# Me-Motor_Driver_v2_0.net
KiCad netlist of a schematic drawn in EAGLE
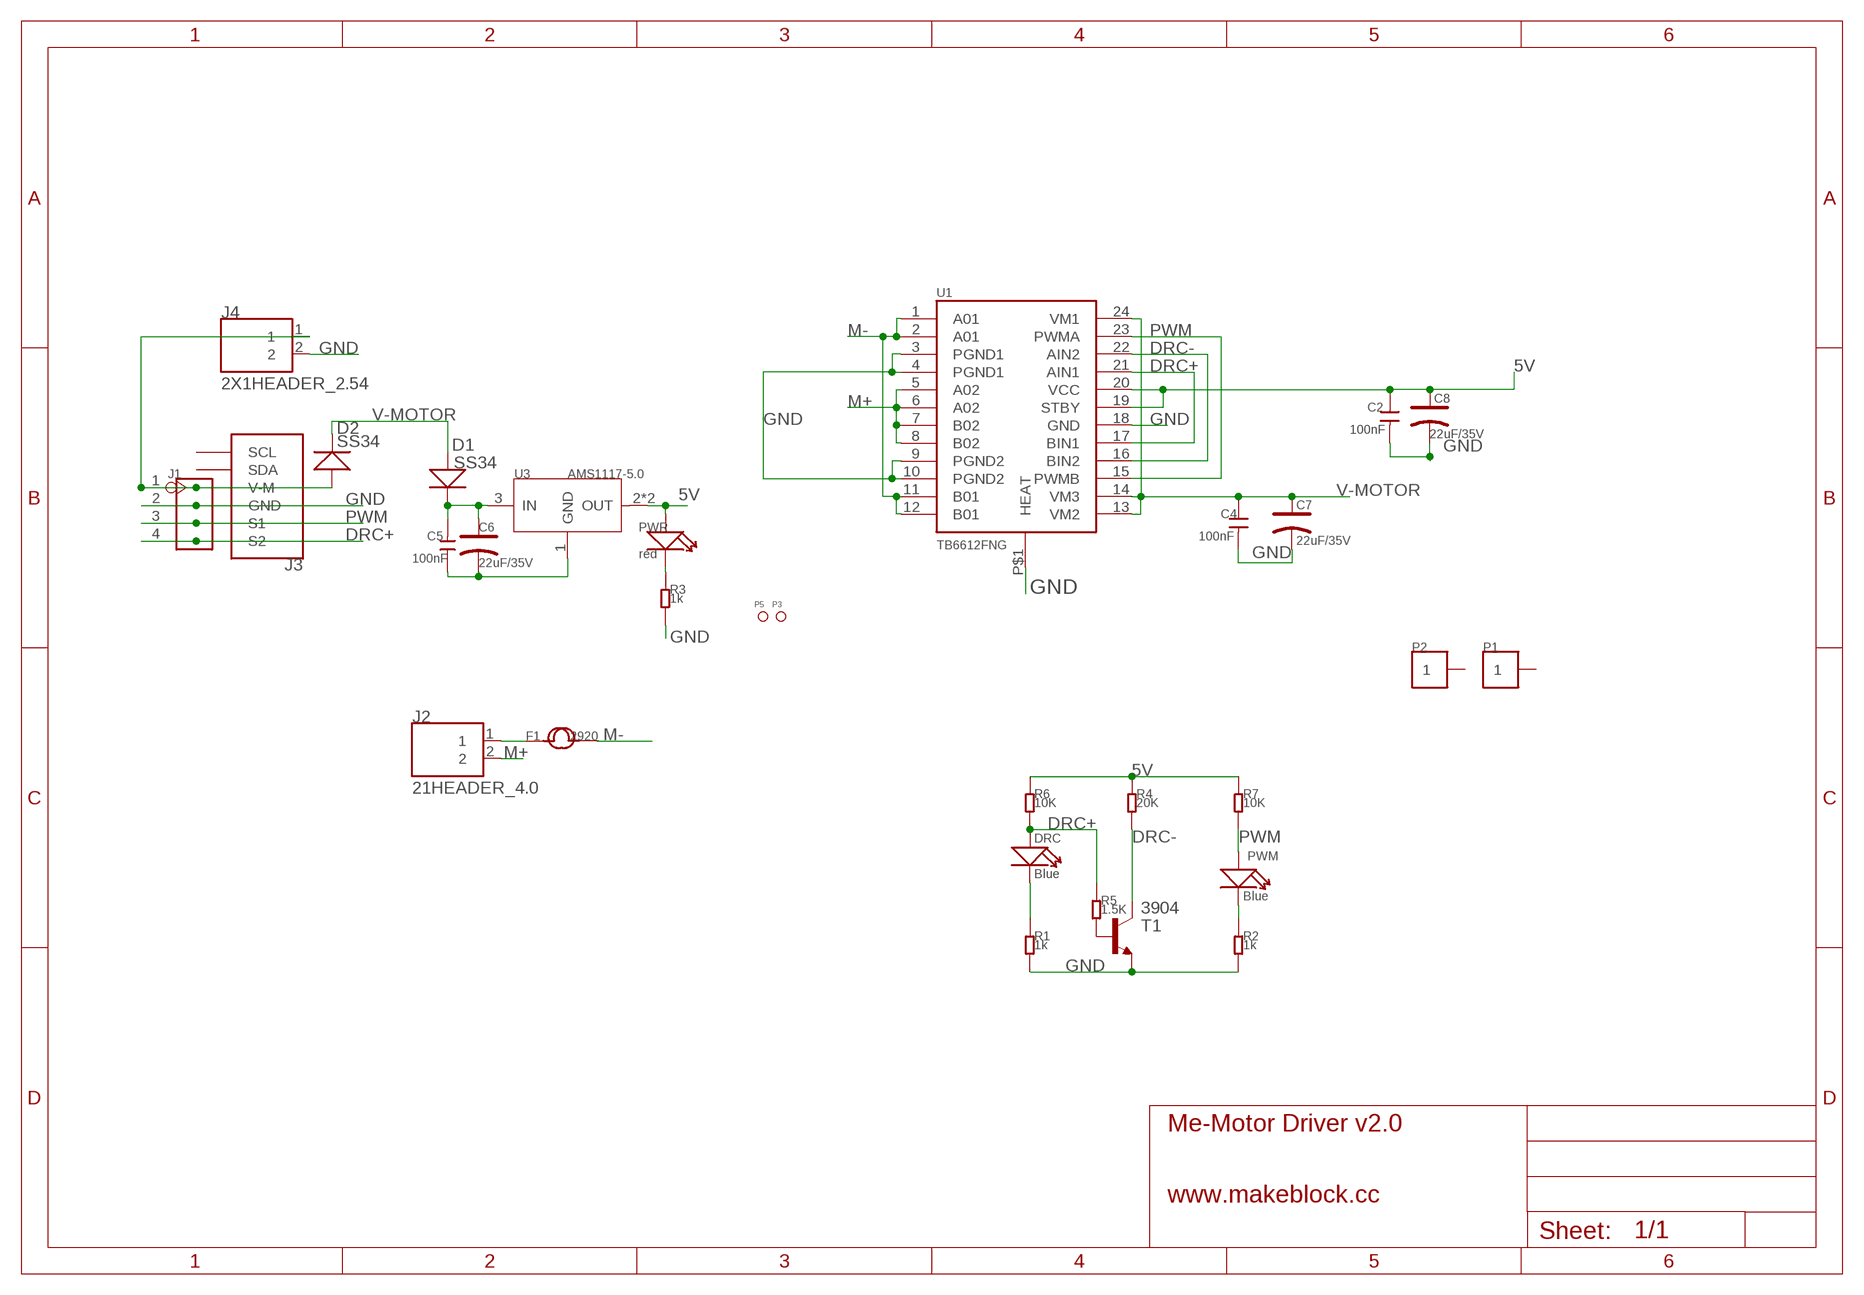
[diagram p0: schematic, sheet 1]

(export (version "E")
  (design (tool "Eeschema 10.0.6"))
  (components
    (comp (ref "C2")
      (value "100nF")
      (footprint "eagle-import:0603_S")
      (libsource (lib "eagle-import") (part "006-C3035"))
    )
    (comp (ref "C4")
      (value "100nF")
      (footprint "eagle-import:0603_S")
      (libsource (lib "eagle-import") (part "006-C3035"))
    )
    (comp (ref "C5")
      (value "100nF")
      (footprint "eagle-import:0603")
      (libsource (lib "eagle-import") (part "C-0603"))
    )
    (comp (ref "C6")
      (value "22uF/35V")
      (footprint "eagle-import:ELECTRO-SMD-B-4.8MM")
      (libsource (lib "eagle-import") (part "CAP-ELECTRO-B"))
    )
    (comp (ref "C7")
      (value "22uF/35V")
      (footprint "eagle-import:ELECTRO-SMD-B-4.8MM")
      (libsource (lib "eagle-import") (part "CAP-ELECTRO-B"))
    )
    (comp (ref "C8")
      (value "22uF/35V")
      (footprint "eagle-import:ELECTRO-SMD-B-4.8MM")
      (libsource (lib "eagle-import") (part "CAP-ELECTRO-B"))
    )
    (comp (ref "D1")
      (value "SS34")
      (footprint "eagle-import:D2010")
      (libsource (lib "eagle-import") (part "D'SMA'"))
    )
    (comp (ref "D2")
      (value "SS34")
      (footprint "eagle-import:D2010")
      (libsource (lib "eagle-import") (part "D'SMA'"))
    )
    (comp (ref "DRC")
      (value "Blue")
      (footprint "eagle-import:LED-0603")
      (libsource (lib "eagle-import") (part "LED'0603'"))
    )
    (comp (ref "F1")
      (value "2920")
      (footprint "eagle-import:2920")
      (libsource (lib "eagle-import") (part "2920"))
    )
    (comp (ref "J1")
      (value "HEADER-4P-60/35MIL")
      (footprint "eagle-import:4P-65_35MIL")
      (libsource (lib "eagle-import") (part "HEADER-4P-60/35MIL"))
    )
    (comp (ref "J2")
      (value "21HEADER_4.0")
      (footprint "eagle-import:2_1HEADER_4.0")
      (libsource (lib "eagle-import") (part "21HEADER_4.0"))
    )
    (comp (ref "J3")
      (value "RJ11-6P6C-MOTOR")
      (footprint "eagle-import:RJ11-6P6C")
      (libsource (lib "eagle-import") (part "RJ11-6P6C-MOTOR"))
    )
    (comp (ref "J4")
      (value "2X1HEADER_2.54")
      (footprint "eagle-import:2X1HEADER_2.54")
      (libsource (lib "eagle-import") (part "2X1HEADER_2.54"))
    )
    (comp (ref "P1")
      (value "PAD-1P-4MM")
      (footprint "eagle-import:HOLE-01")
      (libsource (lib "eagle-import") (part "PAD-1P-4MM"))
    )
    (comp (ref "P2")
      (value "PAD-1P-4MM")
      (footprint "eagle-import:HOLE-01")
      (libsource (lib "eagle-import") (part "PAD-1P-4MM"))
    )
    (comp (ref "P3")
      (value "PAD-MARK")
      (footprint "eagle-import:ROUND-MARK-1.0")
      (fields (field (name "PARTNO") "DNP") (field (name "PARTNO_1") "DNP"))
      (libsource (lib "eagle-import") (part "PAD-MARK"))
    )
    (comp (ref "P5")
      (value "PAD-MARK")
      (footprint "eagle-import:ROUND-MARK-1.0")
      (fields (field (name "PARTNO") "DNP"))
      (libsource (lib "eagle-import") (part "PAD-MARK"))
    )
    (comp (ref "PWM")
      (value "Blue")
      (footprint "eagle-import:LED-0603")
      (libsource (lib "eagle-import") (part "LED'0603'"))
    )
    (comp (ref "PWR")
      (value "red")
      (footprint "eagle-import:LED-0603")
      (libsource (lib "eagle-import") (part "LED'0603'"))
    )
    (comp (ref "R1")
      (value "1k")
      (footprint "eagle-import:0603")
      (libsource (lib "eagle-import") (part "R-0603"))
    )
    (comp (ref "R2")
      (value "1k")
      (footprint "eagle-import:0603")
      (libsource (lib "eagle-import") (part "R-0603"))
    )
    (comp (ref "R3")
      (value "1k")
      (footprint "eagle-import:0603")
      (libsource (lib "eagle-import") (part "R-0603"))
    )
    (comp (ref "R4")
      (value "20K")
      (footprint "eagle-import:0603")
      (libsource (lib "eagle-import") (part "R-0603"))
    )
    (comp (ref "R5")
      (value "1.5K")
      (footprint "eagle-import:0603")
      (libsource (lib "eagle-import") (part "R-0603"))
    )
    (comp (ref "R6")
      (value "10K")
      (footprint "eagle-import:0603")
      (libsource (lib "eagle-import") (part "R-0603"))
    )
    (comp (ref "R7")
      (value "10K")
      (footprint "eagle-import:0603")
      (libsource (lib "eagle-import") (part "R-0603"))
    )
    (comp (ref "T1")
      (value "3904")
      (footprint "eagle-import:3904")
      (libsource (lib "eagle-import") (part "3904"))
    )
    (comp (ref "U1")
      (value "TB6612FNG")
      (footprint "eagle-import:SSOP24")
      (libsource (lib "eagle-import") (part "TB6612FNG"))
    )
    (comp (ref "U3")
      (value "AMS1117-5.0")
      (footprint "eagle-import:SOT-223")
      (libsource (lib "eagle-import") (part "LD1117S"))
    )
  )
  (nets
    (net (code "1") (name "/5V") (class "Default")
      (node (ref "C2") (pin "1") (pinfunction "1_1") (pintype "passive"))
      (node (ref "C8") (pin "+") (pinfunction "+_+") (pintype "passive"))
      (node (ref "PWR") (pin "+") (pinfunction "+_+") (pintype "passive"))
      (node (ref "R4") (pin "1") (pinfunction "1_1") (pintype "passive"))
      (node (ref "R6") (pin "1") (pinfunction "1_1") (pintype "passive"))
      (node (ref "R7") (pin "1") (pinfunction "1_1") (pintype "passive"))
      (node (ref "U1") (pin "19") (pinfunction "STBY_19") (pintype "bidirectional"))
      (node (ref "U1") (pin "20") (pinfunction "VCC_20") (pintype "bidirectional"))
      (node (ref "U3") (pin "2") (pinfunction "OUT_2") (pintype "bidirectional"))
      (node (ref "U3") (pin "TER") (pinfunction "OUT_TER") (pintype "bidirectional"))
    )
    (net (code "2") (name "/DRC+") (class "Default")
      (node (ref "DRC") (pin "+") (pinfunction "+_+") (pintype "passive"))
      (node (ref "J1") (pin "4") (pinfunction "P$4_4") (pintype "bidirectional"))
      (node (ref "J3") (pin "6") (pinfunction "S2_6") (pintype "bidirectional"))
      (node (ref "R5") (pin "1") (pinfunction "1_1") (pintype "passive"))
      (node (ref "R6") (pin "2") (pinfunction "2_2") (pintype "passive"))
      (node (ref "U1") (pin "17") (pinfunction "BIN1_17") (pintype "bidirectional"))
      (node (ref "U1") (pin "21") (pinfunction "AIN1_21") (pintype "bidirectional"))
    )
    (net (code "3") (name "/DRC-") (class "Default")
      (node (ref "R4") (pin "2") (pinfunction "2_2") (pintype "passive"))
      (node (ref "T1") (pin "3") (pinfunction "C_3") (pintype "passive"))
      (node (ref "U1") (pin "16") (pinfunction "BIN2_16") (pintype "bidirectional"))
      (node (ref "U1") (pin "22") (pinfunction "AIN2_22") (pintype "bidirectional"))
    )
    (net (code "4") (name "/GND") (class "Default")
      (node (ref "C2") (pin "2") (pinfunction "2_2") (pintype "passive"))
      (node (ref "C4") (pin "2") (pinfunction "2_2") (pintype "passive"))
      (node (ref "C5") (pin "1") (pinfunction "1_1") (pintype "passive"))
      (node (ref "C6") (pin "-") (pinfunction "-_-") (pintype "passive"))
      (node (ref "C7") (pin "-") (pinfunction "-_-") (pintype "passive"))
      (node (ref "C8") (pin "-") (pinfunction "-_-") (pintype "passive"))
      (node (ref "J1") (pin "2") (pinfunction "P$2_2") (pintype "bidirectional"))
      (node (ref "J3") (pin "4") (pinfunction "GND_4") (pintype "bidirectional"))
      (node (ref "J4") (pin "2") (pinfunction "2_2") (pintype "bidirectional"))
      (node (ref "R1") (pin "2") (pinfunction "2_2") (pintype "passive"))
      (node (ref "R2") (pin "2") (pinfunction "2_2") (pintype "passive"))
      (node (ref "R3") (pin "2") (pinfunction "2_2") (pintype "passive"))
      (node (ref "T1") (pin "2") (pinfunction "E_2") (pintype "passive"))
      (node (ref "U1") (pin "10") (pinfunction "PGND2_10") (pintype "bidirectional"))
      (node (ref "U1") (pin "18") (pinfunction "GND_18") (pintype "bidirectional"))
      (node (ref "U1") (pin "3") (pinfunction "PGND1_3") (pintype "bidirectional"))
      (node (ref "U1") (pin "4") (pinfunction "PGND1_4") (pintype "bidirectional"))
      (node (ref "U1") (pin "9") (pinfunction "PGND2_9") (pintype "bidirectional"))
      (node (ref "U1") (pin "P$1") (pinfunction "HEAT_P$1") (pintype "bidirectional"))
      (node (ref "U3") (pin "1") (pinfunction "GND_1") (pintype "bidirectional"))
    )
    (net (code "5") (name "/M+") (class "Default")
      (node (ref "J2") (pin "2") (pinfunction "2_2") (pintype "bidirectional"))
      (node (ref "U1") (pin "5") (pinfunction "A02_5") (pintype "bidirectional"))
      (node (ref "U1") (pin "6") (pinfunction "A02_6") (pintype "bidirectional"))
      (node (ref "U1") (pin "7") (pinfunction "B02_7") (pintype "bidirectional"))
      (node (ref "U1") (pin "8") (pinfunction "B02_8") (pintype "bidirectional"))
    )
    (net (code "6") (name "/M-") (class "Default")
      (node (ref "F1") (pin "2") (pinfunction "2_2") (pintype "bidirectional"))
      (node (ref "U1") (pin "1") (pinfunction "A01_1") (pintype "bidirectional"))
      (node (ref "U1") (pin "11") (pinfunction "B01_11") (pintype "bidirectional"))
      (node (ref "U1") (pin "12") (pinfunction "B01_12") (pintype "bidirectional"))
      (node (ref "U1") (pin "2") (pinfunction "A01_2") (pintype "bidirectional"))
    )
    (net (code "7") (name "/PWM") (class "Default")
      (node (ref "J1") (pin "3") (pinfunction "P$3_3") (pintype "bidirectional"))
      (node (ref "J3") (pin "5") (pinfunction "S1_5") (pintype "bidirectional"))
      (node (ref "PWM") (pin "+") (pinfunction "+_+") (pintype "passive"))
      (node (ref "R7") (pin "2") (pinfunction "2_2") (pintype "passive"))
      (node (ref "U1") (pin "15") (pinfunction "PWMB_15") (pintype "bidirectional"))
      (node (ref "U1") (pin "23") (pinfunction "PWMA_23") (pintype "bidirectional"))
    )
    (net (code "8") (name "/V-MOTOR") (class "Default")
      (node (ref "C4") (pin "1") (pinfunction "1_1") (pintype "passive"))
      (node (ref "C7") (pin "+") (pinfunction "+_+") (pintype "passive"))
      (node (ref "D1") (pin "+") (pinfunction "+_+") (pintype "passive"))
      (node (ref "D2") (pin "-") (pinfunction "-_-") (pintype "passive"))
      (node (ref "U1") (pin "13") (pinfunction "VM2_13") (pintype "bidirectional"))
      (node (ref "U1") (pin "14") (pinfunction "VM3_14") (pintype "bidirectional"))
      (node (ref "U1") (pin "24") (pinfunction "VM1_24") (pintype "bidirectional"))
    )
    (net (code "9") (name "Net-(DRC-Pad-)") (class "Default")
      (node (ref "DRC") (pin "-") (pinfunction "-_-") (pintype "passive"))
      (node (ref "R1") (pin "1") (pinfunction "1_1") (pintype "passive"))
    )
    (net (code "10") (name "Net-(F1-Pad1)") (class "Default")
      (node (ref "F1") (pin "1") (pinfunction "1_1") (pintype "bidirectional"))
      (node (ref "J2") (pin "1") (pinfunction "1_1") (pintype "bidirectional"))
    )
    (net (code "11") (name "Net-(J1-P$1)") (class "Default")
      (node (ref "D2") (pin "+") (pinfunction "+_+") (pintype "passive"))
      (node (ref "J1") (pin "1") (pinfunction "P$1_1") (pintype "bidirectional"))
      (node (ref "J3") (pin "3") (pinfunction "V-M_3") (pintype "bidirectional"))
      (node (ref "J4") (pin "1") (pinfunction "1_1") (pintype "bidirectional"))
    )
    (net (code "12") (name "Net-(PWM-Pad-)") (class "Default")
      (node (ref "PWM") (pin "-") (pinfunction "-_-") (pintype "passive"))
      (node (ref "R2") (pin "1") (pinfunction "1_1") (pintype "passive"))
    )
    (net (code "13") (name "Net-(PWR-Pad-)") (class "Default")
      (node (ref "PWR") (pin "-") (pinfunction "-_-") (pintype "passive"))
      (node (ref "R3") (pin "1") (pinfunction "1_1") (pintype "passive"))
    )
    (net (code "14") (name "Net-(T1-B)") (class "Default")
      (node (ref "R5") (pin "2") (pinfunction "2_2") (pintype "passive"))
      (node (ref "T1") (pin "1") (pinfunction "B_1") (pintype "passive"))
    )
    (net (code "15") (name "Net-(U3-IN)") (class "Default")
      (node (ref "C5") (pin "2") (pinfunction "2_2") (pintype "passive"))
      (node (ref "C6") (pin "+") (pinfunction "+_+") (pintype "passive"))
      (node (ref "D1") (pin "-") (pinfunction "-_-") (pintype "passive"))
      (node (ref "U3") (pin "3") (pinfunction "IN_3") (pintype "bidirectional"))
    )
    (net (code "16") (name "unconnected-(J3-SCL-Pad1)") (class "Default")
      (node (ref "J3") (pin "1") (pinfunction "SCL_1") (pintype "bidirectional"))
    )
    (net (code "17") (name "unconnected-(J3-SDA-Pad2)") (class "Default")
      (node (ref "J3") (pin "2") (pinfunction "SDA_2") (pintype "bidirectional"))
    )
    (net (code "18") (name "unconnected-(P1-Pad1)") (class "Default")
      (node (ref "P1") (pin "1") (pinfunction "1_1") (pintype "bidirectional"))
    )
    (net (code "19") (name "unconnected-(P2-Pad1)") (class "Default")
      (node (ref "P2") (pin "1") (pinfunction "1_1") (pintype "bidirectional"))
    )
  )
)
